# H_bridge.net
KiCad netlist of a schematic drawn in Altium Designer
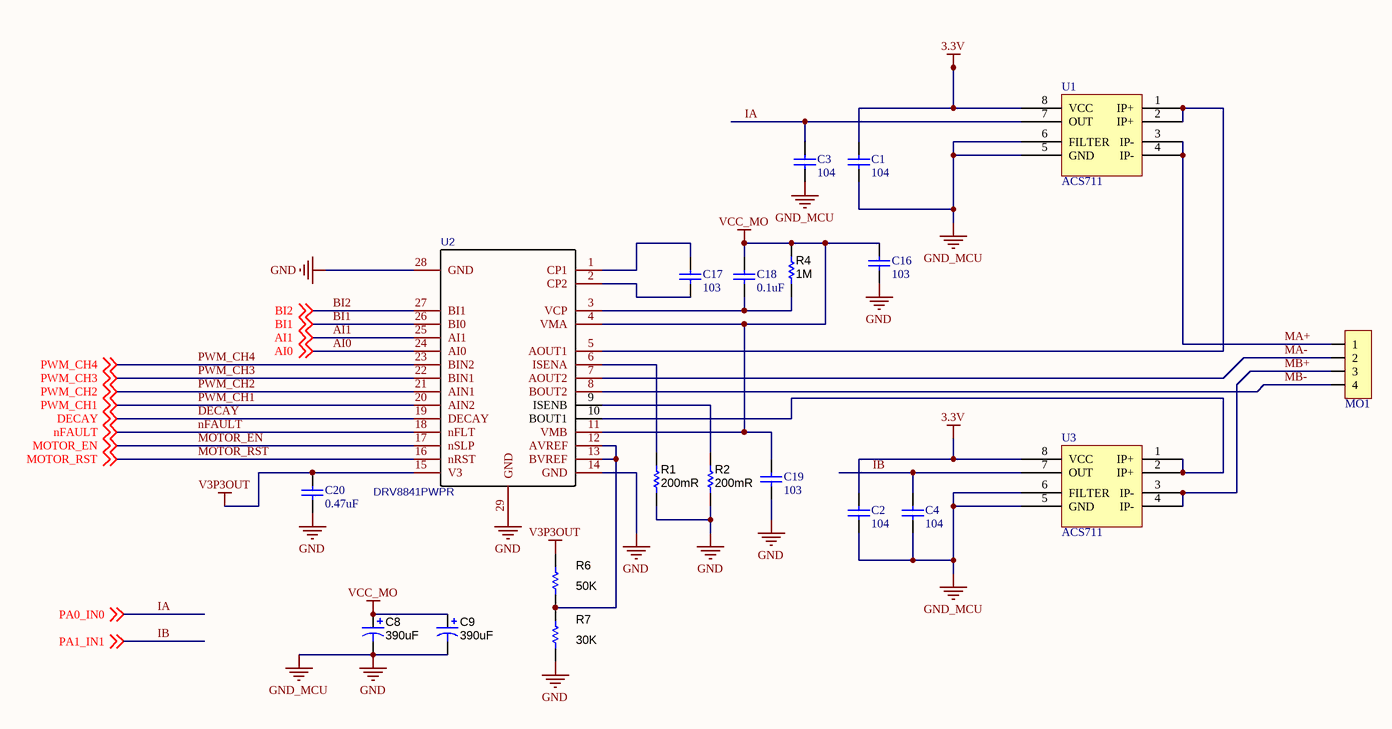
[diagram p0: H_bridge.SchDoc]

(export (version "E")
  (design (tool "Eeschema 10.0.6"))
  (components
    (comp (ref "C1")
      (value "104")
      (footprint "0805_HV")
      (description "Ceramic Chip Capacitor - Standard")
      (fields (field (name "PUBLISHER") "Altium Limited"))
      (libsource (lib "mySch") (part "Capacitor 0805"))
    )
    (comp (ref "C2")
      (value "104")
      (footprint "0805_HV")
      (description "Ceramic Chip Capacitor - Standard")
      (fields (field (name "PUBLISHER") "Altium Limited"))
      (libsource (lib "mySch") (part "Capacitor 0805"))
    )
    (comp (ref "C3")
      (value "104")
      (footprint "0805_HV")
      (description "Ceramic Chip Capacitor - Standard")
      (fields (field (name "PUBLISHER") "Altium Limited"))
      (libsource (lib "mySch") (part "Capacitor 0805"))
    )
    (comp (ref "C4")
      (value "104")
      (footprint "0805_HV")
      (description "Ceramic Chip Capacitor - Standard")
      (fields (field (name "PUBLISHER") "Altium Limited"))
      (libsource (lib "mySch") (part "Capacitor 0805"))
    )
    (comp (ref "C8")
      (value "390uF")
      (footprint "CP1/3.0")
      (fields
        (field (name "PARTNUMBER") "UHW1H391MPD6")
        (field (name "MANUFACTURER") "Nichicon")
        (field (name "VALUEDISPLAYED") "390uF")
        (field (name "PUBLISHER") "Texas Instruments")
      )
      (libsource (lib "mySch") (part "Capacitor TuHoa"))
    )
    (comp (ref "C9")
      (value "390uF")
      (footprint "CP1/3.0")
      (fields
        (field (name "PARTNUMBER") "UHW1H391MPD6")
        (field (name "MANUFACTURER") "Nichicon")
        (field (name "VALUEDISPLAYED") "390uF")
        (field (name "PUBLISHER") "Texas Instruments")
      )
      (libsource (lib "mySch") (part "Capacitor TuHoa"))
    )
    (comp (ref "C16")
      (value "103")
      (footprint "0805_HV")
      (description "Ceramic Chip Capacitor - Standard")
      (fields (field (name "PUBLISHER") "Altium Limited"))
      (libsource (lib "mySch") (part "Capacitor 0805"))
    )
    (comp (ref "C17")
      (value "103")
      (footprint "0805_HV")
      (description "Ceramic Chip Capacitor - Standard")
      (fields (field (name "PUBLISHER") "Altium Limited"))
      (libsource (lib "mySch") (part "Capacitor 0805"))
    )
    (comp (ref "C18")
      (value "0.1uF")
      (footprint "0805_HV")
      (description "Ceramic Chip Capacitor - Standard")
      (fields (field (name "PUBLISHER") "Altium Limited"))
      (libsource (lib "mySch") (part "Capacitor 0805"))
    )
    (comp (ref "C19")
      (value "103")
      (footprint "0805_HV")
      (description "Ceramic Chip Capacitor - Standard")
      (fields (field (name "PUBLISHER") "Altium Limited"))
      (libsource (lib "mySch") (part "Capacitor 0805"))
    )
    (comp (ref "C20")
      (value "0.47uF")
      (footprint "0805_HV")
      (description "Ceramic Chip Capacitor - Standard")
      (fields (field (name "PUBLISHER") "Altium Limited"))
      (libsource (lib "mySch") (part "Capacitor 0805"))
    )
    (comp (ref "MO1")
      (value "Header 4_MH")
      (footprint "HEADER 4")
      (description "Header 4P XH2.54 thẳng")
      (libsource (lib "MH_DA_THU_VIEN_16122016") (part "Header 4_MH"))
    )
    (comp (ref "R1")
      (value "RT0603DRE07140KL")
      (footprint "1210")
      (description "RES, 140 k, 0.5%, 0.1 W, 0603")
      (fields
        (field (name "VALUEDISPLAYED") "200mR")
        (field (name "MANUFACTURER") "Yageo America")
        (field (name "PUBLISHER") "Texas Instruments")
      )
      (libsource (lib "Resistor_0603") (part "RT0603DRE07140KL"))
    )
    (comp (ref "R2")
      (value "RT0603DRE07140KL")
      (footprint "1210")
      (description "RES, 140 k, 0.5%, 0.1 W, 0603")
      (fields
        (field (name "VALUEDISPLAYED") "200mR")
        (field (name "MANUFACTURER") "Yageo America")
        (field (name "PUBLISHER") "Texas Instruments")
      )
      (libsource (lib "Resistor_0603") (part "RT0603DRE07140KL"))
    )
    (comp (ref "R4")
      (value "1M")
      (footprint "0805_HV")
      (description "RES, 100, 1%, 0.1 W, 0402")
      (fields
        (field (name "PARTNUMBER") "ERJ-2RKF1000X")
        (field (name "MANUFACTURER") "Panasonic")
        (field (name "PUBLISHER") "Texas Instruments")
      )
      (libsource (lib "mySch") (part "R nho"))
    )
    (comp (ref "R6")
      (value "50K")
      (footprint "0805_HV")
      (description "RES, 100, 1%, 0.1 W, 0402")
      (fields
        (field (name "PARTNUMBER") "ERJ-2RKF1000X")
        (field (name "MANUFACTURER") "Panasonic")
        (field (name "PUBLISHER") "Texas Instruments")
      )
      (libsource (lib "mySch") (part "R nho"))
    )
    (comp (ref "R7")
      (value "30K")
      (footprint "0805_HV")
      (description "RES, 100, 1%, 0.1 W, 0402")
      (fields
        (field (name "PARTNUMBER") "ERJ-2RKF1000X")
        (field (name "MANUFACTURER") "Panasonic")
        (field (name "PUBLISHER") "Texas Instruments")
      )
      (libsource (lib "mySch") (part "R nho"))
    )
    (comp (ref "U1") (value "ACS711") (footprint "SOP 8") (libsource (lib "mySch") (part "ACS712")))
    (comp (ref "U2")
      (value "DRV8841PWPR")
      (footprint "TSSOP-28EP")
      (fields (field (name "BOM_SUPPLIER PART") "C36542"))
      (libsource (lib "Schlib1") (part "DRV8841PWPR"))
    )
    (comp (ref "U3") (value "ACS711") (footprint "SOP 8") (libsource (lib "mySch") (part "ACS712")))
  )
  (nets
    (net (code "1") (name "/MA+") (class "Default")
      (node (ref "MO1") (pin "1") (pinfunction "1_1") (pintype "passive"))
      (node (ref "U1") (pin "3") (pinfunction "IP-_3") (pintype "passive"))
      (node (ref "U1") (pin "4") (pinfunction "IP-_4") (pintype "passive"))
    )
    (net (code "2") (name "/MA-") (class "Default")
      (node (ref "MO1") (pin "2") (pinfunction "2_2") (pintype "passive"))
      (node (ref "U2") (pin "7") (pinfunction "AOUT2_7") (pintype "passive"))
    )
    (net (code "3") (name "/MB+") (class "Default")
      (node (ref "MO1") (pin "3") (pinfunction "3_3") (pintype "passive"))
      (node (ref "U3") (pin "3") (pinfunction "IP-_3") (pintype "passive"))
      (node (ref "U3") (pin "4") (pinfunction "IP-_4") (pintype "passive"))
    )
    (net (code "4") (name "/MB-") (class "Default")
      (node (ref "MO1") (pin "4") (pinfunction "4_4") (pintype "passive"))
      (node (ref "U2") (pin "8") (pinfunction "BOUT2_8") (pintype "passive"))
    )
    (net (code "5") (name "3.3V") (class "Default")
      (node (ref "C1") (pin "2") (pinfunction "2_2") (pintype "passive"))
      (node (ref "C2") (pin "2") (pinfunction "2_2") (pintype "passive"))
      (node (ref "U1") (pin "8") (pinfunction "VCC_8") (pintype "passive"))
      (node (ref "U3") (pin "8") (pinfunction "VCC_8") (pintype "passive"))
    )
    (net (code "6") (name "AI0") (class "Default")
      (node (ref "U2") (pin "24") (pinfunction "AI0_24") (pintype "passive"))
    )
    (net (code "7") (name "AI1") (class "Default")
      (node (ref "U2") (pin "25") (pinfunction "AI1_25") (pintype "passive"))
    )
    (net (code "8") (name "BI1") (class "Default")
      (node (ref "U2") (pin "26") (pinfunction "BI0_26") (pintype "passive"))
    )
    (net (code "9") (name "BI2") (class "Default")
      (node (ref "U2") (pin "27") (pinfunction "BI1_27") (pintype "passive"))
    )
    (net (code "10") (name "DECAY") (class "Default")
      (node (ref "U2") (pin "19") (pinfunction "DECAY_19") (pintype "passive"))
    )
    (net (code "11") (name "GND") (class "Default")
      (node (ref "C1") (pin "1") (pinfunction "1_1") (pintype "passive"))
      (node (ref "C16") (pin "1") (pinfunction "1_1") (pintype "passive"))
      (node (ref "C19") (pin "1") (pinfunction "1_1") (pintype "passive"))
      (node (ref "C2") (pin "1") (pinfunction "1_1") (pintype "passive"))
      (node (ref "C20") (pin "1") (pinfunction "1_1") (pintype "passive"))
      (node (ref "C3") (pin "1") (pinfunction "1_1") (pintype "passive"))
      (node (ref "C4") (pin "1") (pinfunction "1_1") (pintype "passive"))
      (node (ref "C8") (pin "2") (pinfunction "-_2") (pintype "passive"))
      (node (ref "C9") (pin "2") (pinfunction "-_2") (pintype "passive"))
      (node (ref "R1") (pin "1") (pinfunction "1_1") (pintype "passive"))
      (node (ref "R2") (pin "1") (pinfunction "1_1") (pintype "passive"))
      (node (ref "R7") (pin "1") (pinfunction "1_1") (pintype "passive"))
      (node (ref "U1") (pin "5") (pinfunction "GND_5") (pintype "passive"))
      (node (ref "U1") (pin "6") (pinfunction "FILTER_6") (pintype "passive"))
      (node (ref "U2") (pin "14") (pinfunction "GND_14") (pintype "passive"))
      (node (ref "U2") (pin "28") (pinfunction "GND_28") (pintype "passive"))
      (node (ref "U2") (pin "29") (pinfunction "GND_29") (pintype "passive"))
      (node (ref "U3") (pin "5") (pinfunction "GND_5") (pintype "passive"))
      (node (ref "U3") (pin "6") (pinfunction "FILTER_6") (pintype "passive"))
    )
    (net (code "12") (name "MOTOR_EN") (class "Default")
      (node (ref "U2") (pin "17") (pinfunction "nSLP_17") (pintype "passive"))
    )
    (net (code "13") (name "MOTOR_RST") (class "Default")
      (node (ref "U2") (pin "16") (pinfunction "nRST_16") (pintype "passive"))
    )
    (net (code "14") (name "Net-(U2-AOUT1)") (class "Default")
      (node (ref "U1") (pin "1") (pinfunction "IP+_1") (pintype "passive"))
      (node (ref "U1") (pin "2") (pinfunction "IP+_2") (pintype "passive"))
      (node (ref "U2") (pin "5") (pinfunction "AOUT1_5") (pintype "passive"))
    )
    (net (code "15") (name "Net-(U2-AVREF)") (class "Default")
      (node (ref "R6") (pin "1") (pinfunction "1_1") (pintype "passive"))
      (node (ref "R7") (pin "2") (pinfunction "2_2") (pintype "passive"))
      (node (ref "U2") (pin "12") (pinfunction "AVREF_12") (pintype "passive"))
      (node (ref "U2") (pin "13") (pinfunction "BVREF_13") (pintype "passive"))
    )
    (net (code "16") (name "Net-(U2-BOUT1)") (class "Default")
      (node (ref "U2") (pin "10") (pinfunction "BOUT1_10") (pintype "passive"))
      (node (ref "U3") (pin "1") (pinfunction "IP+_1") (pintype "passive"))
      (node (ref "U3") (pin "2") (pinfunction "IP+_2") (pintype "passive"))
    )
    (net (code "17") (name "Net-(U2-CP1)") (class "Default")
      (node (ref "C17") (pin "2") (pinfunction "2_2") (pintype "passive"))
      (node (ref "U2") (pin "1") (pinfunction "CP1_1") (pintype "passive"))
    )
    (net (code "18") (name "Net-(U2-CP2)") (class "Default")
      (node (ref "C17") (pin "1") (pinfunction "1_1") (pintype "passive"))
      (node (ref "U2") (pin "2") (pinfunction "CP2_2") (pintype "passive"))
    )
    (net (code "19") (name "Net-(U2-ISENA)") (class "Default")
      (node (ref "R1") (pin "2") (pinfunction "2_2") (pintype "passive"))
      (node (ref "U2") (pin "6") (pinfunction "ISENA_6") (pintype "passive"))
    )
    (net (code "20") (name "Net-(U2-ISENB)") (class "Default")
      (node (ref "R2") (pin "2") (pinfunction "2_2") (pintype "passive"))
      (node (ref "U2") (pin "9") (pinfunction "ISENB_9") (pintype "passive"))
    )
    (net (code "21") (name "Net-(U2-VCP)") (class "Default")
      (node (ref "C18") (pin "1") (pinfunction "1_1") (pintype "passive"))
      (node (ref "R4") (pin "1") (pinfunction "1_1") (pintype "passive"))
      (node (ref "U2") (pin "3") (pinfunction "VCP_3") (pintype "passive"))
    )
    (net (code "22") (name "PA0_IN0") (class "Default")
      (node (ref "C3") (pin "2") (pinfunction "2_2") (pintype "passive"))
      (node (ref "U1") (pin "7") (pinfunction "OUT_7") (pintype "passive"))
    )
    (net (code "23") (name "PA1_IN1") (class "Default")
      (node (ref "C4") (pin "2") (pinfunction "2_2") (pintype "passive"))
      (node (ref "U3") (pin "7") (pinfunction "OUT_7") (pintype "passive"))
    )
    (net (code "24") (name "PWM_CH1") (class "Default")
      (node (ref "U2") (pin "20") (pinfunction "AIN2_20") (pintype "passive"))
    )
    (net (code "25") (name "PWM_CH2") (class "Default")
      (node (ref "U2") (pin "21") (pinfunction "AIN1_21") (pintype "passive"))
    )
    (net (code "26") (name "PWM_CH3") (class "Default")
      (node (ref "U2") (pin "22") (pinfunction "BIN1_22") (pintype "passive"))
    )
    (net (code "27") (name "PWM_CH4") (class "Default")
      (node (ref "U2") (pin "23") (pinfunction "BIN2_23") (pintype "passive"))
    )
    (net (code "28") (name "V3P3OUT") (class "Default")
      (node (ref "C20") (pin "2") (pinfunction "2_2") (pintype "passive"))
      (node (ref "R6") (pin "2") (pinfunction "2_2") (pintype "passive"))
      (node (ref "U2") (pin "15") (pinfunction "V3_15") (pintype "passive"))
    )
    (net (code "29") (name "VCC_MO") (class "Default")
      (node (ref "C16") (pin "2") (pinfunction "2_2") (pintype "passive"))
      (node (ref "C18") (pin "2") (pinfunction "2_2") (pintype "passive"))
      (node (ref "C19") (pin "2") (pinfunction "2_2") (pintype "passive"))
      (node (ref "C8") (pin "1") (pinfunction "+_1") (pintype "passive"))
      (node (ref "C9") (pin "1") (pinfunction "+_1") (pintype "passive"))
      (node (ref "R4") (pin "2") (pinfunction "2_2") (pintype "passive"))
      (node (ref "U2") (pin "11") (pinfunction "VMB_11") (pintype "passive"))
      (node (ref "U2") (pin "4") (pinfunction "VMA_4") (pintype "passive"))
    )
    (net (code "30") (name "nFAULT") (class "Default")
      (node (ref "U2") (pin "18") (pinfunction "nFLT_18") (pintype "passive"))
    )
  )
)
